# 02_V5_IO1.net
KiCad netlist of a schematic drawn in Altium Designer
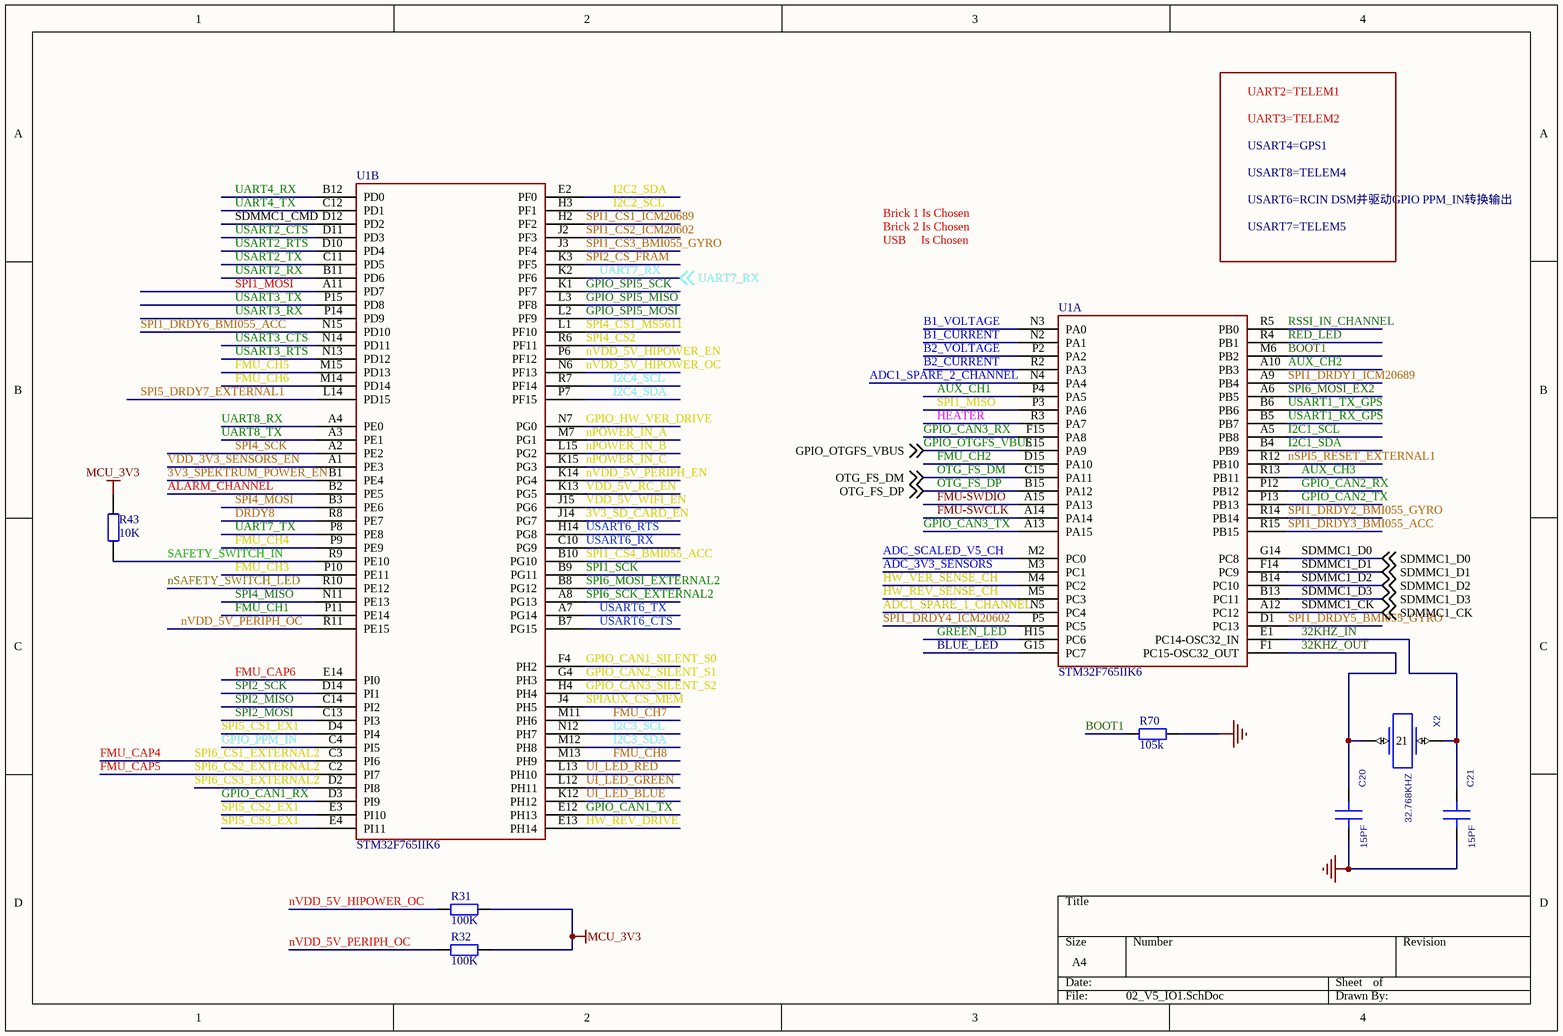
[diagram p0: 02_V5_IO1.SchDoc]

(export (version "E")
  (design (tool "Eeschema 10.0.6"))
  (components
    (comp (ref "C20") (value "15PF") (footprint "SC0402") (libsource (lib "*") (part "C")))
    (comp (ref "C21") (value "15PF") (footprint "SC0402") (libsource (lib "*") (part "C")))
    (comp (ref "R31")
      (value "100K")
      (description "Resistor")
      (fields (field (name "PUBLISHER") "Altium Limited"))
      (libsource (lib "Miscellaneous Devices") (part "Res2"))
    )
    (comp (ref "R32")
      (value "100K")
      (description "Resistor")
      (fields (field (name "PUBLISHER") "Altium Limited"))
      (libsource (lib "Miscellaneous Devices") (part "Res2"))
    )
    (comp (ref "R43")
      (value "10K")
      (footprint "0402R")
      (description "0402R0R 1%")
      (libsource (lib "CUAV") (part "0402R0R"))
    )
    (comp (ref "R70")
      (value "105k")
      (description "Resistor")
      (fields (field (name "PUBLISHER") "Altium Limited"))
      (libsource (lib "Miscellaneous Devices") (part "Res2"))
    )
    (comp (ref "U1")
      (value "STM32F765IIK6")
      (footprint "UFBGA176")
      (libsource (lib "CUAV") (part "STM32F765IIK6"))
    )
    (comp (ref "X2") (value "32.768KHZ") (footprint "ABS06") (libsource (lib "*") (part "X_0")))
  )
  (nets
    (net (code "1") (name "/3V3_SD_CARD_EN") (class "Default")
      (node (ref "U1") (pin "J14") (pinfunction "PG7_J14") (pintype "passive"))
    )
    (net (code "2") (name "/3V3_SPEKTRUM_POWER_EN") (class "Default")
      (node (ref "U1") (pin "B1") (pinfunction "PE4_B1") (pintype "passive"))
    )
    (net (code "3") (name "/32KHZ_IN") (class "Default")
      (node (ref "C21") (pin "1") (pinfunction "A_1") (pintype "bidirectional"))
      (node (ref "U1") (pin "E1") (pinfunction "PC14-OSC32_IN_E1") (pintype "passive"))
      (node (ref "X2") (pin "1") (pinfunction "1_1") (pintype "bidirectional"))
    )
    (net (code "4") (name "/32KHZ_OUT") (class "Default")
      (node (ref "C20") (pin "1") (pinfunction "A_1") (pintype "bidirectional"))
      (node (ref "U1") (pin "F1") (pinfunction "PC15-OSC32_OUT_F1") (pintype "passive"))
      (node (ref "X2") (pin "2") (pinfunction "2_2") (pintype "bidirectional"))
    )
    (net (code "5") (name "/ADC1_SPARE_1_CHANNEL") (class "Default")
      (node (ref "U1") (pin "N5") (pinfunction "PC4_N5") (pintype "passive"))
    )
    (net (code "6") (name "/ADC1_SPARE_2_CHANNEL") (class "Default")
      (node (ref "U1") (pin "N4") (pinfunction "PA4_N4") (pintype "passive"))
    )
    (net (code "7") (name "/ADC_3V3_SENSORS") (class "Default")
      (node (ref "U1") (pin "M3") (pinfunction "PC1_M3") (pintype "passive"))
    )
    (net (code "8") (name "/ADC_SCALED_V5_CH") (class "Default")
      (node (ref "U1") (pin "M2") (pinfunction "PC0_M2") (pintype "passive"))
    )
    (net (code "9") (name "/ALARM_CHANNEL") (class "Default")
      (node (ref "U1") (pin "B2") (pinfunction "PE5_B2") (pintype "passive"))
    )
    (net (code "10") (name "/AUX_CH1") (class "Default")
      (node (ref "U1") (pin "P4") (pinfunction "PA5_P4") (pintype "passive"))
    )
    (net (code "11") (name "/AUX_CH2") (class "Default")
      (node (ref "U1") (pin "A10") (pinfunction "PB3_A10") (pintype "passive"))
    )
    (net (code "12") (name "/AUX_CH3") (class "Default")
      (node (ref "U1") (pin "R13") (pinfunction "PB11_R13") (pintype "passive"))
    )
    (net (code "13") (name "/B1_CURRENT") (class "Default")
      (node (ref "U1") (pin "N2") (pinfunction "PA1_N2") (pintype "passive"))
    )
    (net (code "14") (name "/B1_VOLTAGE") (class "Default")
      (node (ref "U1") (pin "N3") (pinfunction "PA0_N3") (pintype "passive"))
    )
    (net (code "15") (name "/B2_CURRENT") (class "Default")
      (node (ref "U1") (pin "R2") (pinfunction "PA3_R2") (pintype "passive"))
    )
    (net (code "16") (name "/B2_VOLTAGE") (class "Default")
      (node (ref "U1") (pin "P2") (pinfunction "PA2_P2") (pintype "passive"))
    )
    (net (code "17") (name "/BLUE_LED") (class "Default")
      (node (ref "U1") (pin "G15") (pinfunction "PC7_G15") (pintype "passive"))
    )
    (net (code "18") (name "/BOOT1") (class "Default")
      (node (ref "R70") (pin "1") (pinfunction "1_1") (pintype "passive"))
      (node (ref "U1") (pin "M6") (pinfunction "PB2_M6") (pintype "passive"))
    )
    (net (code "21") (name "/DRDY8") (class "Default")
      (node (ref "U1") (pin "R8") (pinfunction "PE7_R8") (pintype "passive"))
    )
    (net (code "22") (name "/FMU-SWCLK") (class "Default")
      (node (ref "U1") (pin "A14") (pinfunction "PA14_A14") (pintype "passive"))
    )
    (net (code "23") (name "/FMU-SWDIO") (class "Default")
      (node (ref "U1") (pin "A15") (pinfunction "PA13_A15") (pintype "passive"))
    )
    (net (code "24") (name "/FMU_CAP4") (class "Default")
      (node (ref "U1") (pin "C3") (pinfunction "PI6_C3") (pintype "passive"))
    )
    (net (code "25") (name "/FMU_CAP5") (class "Default")
      (node (ref "U1") (pin "C2") (pinfunction "PI7_C2") (pintype "passive"))
    )
    (net (code "26") (name "/FMU_CAP6") (class "Default")
      (node (ref "U1") (pin "E14") (pinfunction "PI0_E14") (pintype "passive"))
    )
    (net (code "27") (name "/FMU_CH1") (class "Default")
      (node (ref "U1") (pin "P11") (pinfunction "PE14_P11") (pintype "passive"))
    )
    (net (code "28") (name "/FMU_CH2") (class "Default")
      (node (ref "U1") (pin "D15") (pinfunction "PA10_D15") (pintype "passive"))
    )
    (net (code "29") (name "/FMU_CH3") (class "Default")
      (node (ref "U1") (pin "P10") (pinfunction "PE11_P10") (pintype "passive"))
    )
    (net (code "30") (name "/FMU_CH4") (class "Default")
      (node (ref "U1") (pin "P9") (pinfunction "PE9_P9") (pintype "passive"))
    )
    (net (code "31") (name "/FMU_CH5") (class "Default")
      (node (ref "U1") (pin "M15") (pinfunction "PD13_M15") (pintype "passive"))
    )
    (net (code "32") (name "/FMU_CH6") (class "Default")
      (node (ref "U1") (pin "M14") (pinfunction "PD14_M14") (pintype "passive"))
    )
    (net (code "33") (name "/FMU_CH7") (class "Default")
      (node (ref "U1") (pin "M11") (pinfunction "PH6_M11") (pintype "passive"))
    )
    (net (code "34") (name "/FMU_CH8") (class "Default")
      (node (ref "U1") (pin "M13") (pinfunction "PH9_M13") (pintype "passive"))
    )
    (net (code "35") (name "/GPIO_CAN1_RX") (class "Default")
      (node (ref "U1") (pin "D3") (pinfunction "PI9_D3") (pintype "passive"))
    )
    (net (code "36") (name "/GPIO_CAN1_SILENT_S0") (class "Default")
      (node (ref "U1") (pin "F4") (pinfunction "PH2_F4") (pintype "passive"))
    )
    (net (code "37") (name "/GPIO_CAN1_TX") (class "Default")
      (node (ref "U1") (pin "E12") (pinfunction "PH13_E12") (pintype "passive"))
    )
    (net (code "38") (name "/GPIO_CAN2_RX") (class "Default")
      (node (ref "U1") (pin "P12") (pinfunction "PB12_P12") (pintype "passive"))
    )
    (net (code "39") (name "/GPIO_CAN2_SILENT_S1") (class "Default")
      (node (ref "U1") (pin "G4") (pinfunction "PH3_G4") (pintype "passive"))
    )
    (net (code "40") (name "/GPIO_CAN2_TX") (class "Default")
      (node (ref "U1") (pin "P13") (pinfunction "PB13_P13") (pintype "passive"))
    )
    (net (code "41") (name "/GPIO_CAN3_RX") (class "Default")
      (node (ref "U1") (pin "F15") (pinfunction "PA8_F15") (pintype "passive"))
    )
    (net (code "42") (name "/GPIO_CAN3_SILENT_S2") (class "Default")
      (node (ref "U1") (pin "H4") (pinfunction "PH4_H4") (pintype "passive"))
    )
    (net (code "43") (name "/GPIO_CAN3_TX") (class "Default")
      (node (ref "U1") (pin "A13") (pinfunction "PA15_A13") (pintype "passive"))
    )
    (net (code "44") (name "/GPIO_HW_VER_DRIVE") (class "Default")
      (node (ref "U1") (pin "N7") (pinfunction "PG0_N7") (pintype "passive"))
    )
    (net (code "45") (name "/GPIO_PPM_IN") (class "Default")
      (node (ref "U1") (pin "C4") (pinfunction "PI5_C4") (pintype "passive"))
    )
    (net (code "46") (name "/GPIO_SPI5_MISO") (class "Default")
      (node (ref "U1") (pin "L3") (pinfunction "PF8_L3") (pintype "passive"))
    )
    (net (code "47") (name "/GPIO_SPI5_MOSI") (class "Default")
      (node (ref "U1") (pin "L2") (pinfunction "PF9_L2") (pintype "passive"))
    )
    (net (code "48") (name "/GPIO_SPI5_SCK") (class "Default")
      (node (ref "U1") (pin "K1") (pinfunction "PF7_K1") (pintype "passive"))
    )
    (net (code "49") (name "/GREEN_LED") (class "Default")
      (node (ref "U1") (pin "H15") (pinfunction "PC6_H15") (pintype "passive"))
    )
    (net (code "50") (name "/HEATER") (class "Default")
      (node (ref "U1") (pin "R3") (pinfunction "PA7_R3") (pintype "passive"))
    )
    (net (code "51") (name "/HW_REV_DRIVE") (class "Default")
      (node (ref "U1") (pin "E13") (pinfunction "PH14_E13") (pintype "passive"))
    )
    (net (code "52") (name "/HW_REV_SENSE_CH") (class "Default")
      (node (ref "U1") (pin "M5") (pinfunction "PC3_M5") (pintype "passive"))
    )
    (net (code "53") (name "/HW_VER_SENSE_CH") (class "Default")
      (node (ref "U1") (pin "M4") (pinfunction "PC2_M4") (pintype "passive"))
    )
    (net (code "54") (name "/I2C1_SCL") (class "Default")
      (node (ref "U1") (pin "A5") (pinfunction "PB8_A5") (pintype "passive"))
    )
    (net (code "55") (name "/I2C1_SDA") (class "Default")
      (node (ref "U1") (pin "B4") (pinfunction "PB9_B4") (pintype "passive"))
    )
    (net (code "56") (name "/I2C2_SCL") (class "Default")
      (node (ref "U1") (pin "H3") (pinfunction "PF1_H3") (pintype "passive"))
    )
    (net (code "57") (name "/I2C2_SDA") (class "Default")
      (node (ref "U1") (pin "E2") (pinfunction "PF0_E2") (pintype "passive"))
    )
    (net (code "58") (name "/I2C3_SCL") (class "Default")
      (node (ref "U1") (pin "N12") (pinfunction "PH7_N12") (pintype "passive"))
    )
    (net (code "59") (name "/I2C3_SDA") (class "Default")
      (node (ref "U1") (pin "M12") (pinfunction "PH8_M12") (pintype "passive"))
    )
    (net (code "60") (name "/I2C4_SCL") (class "Default")
      (node (ref "U1") (pin "R7") (pinfunction "PF14_R7") (pintype "passive"))
    )
    (net (code "61") (name "/I2C4_SDA") (class "Default")
      (node (ref "U1") (pin "P7") (pinfunction "PF15_P7") (pintype "passive"))
    )
    (net (code "62") (name "/RED_LED") (class "Default")
      (node (ref "U1") (pin "R4") (pinfunction "PB1_R4") (pintype "passive"))
    )
    (net (code "63") (name "/RSSI_IN_CHANNEL") (class "Default")
      (node (ref "U1") (pin "R5") (pinfunction "PB0_R5") (pintype "passive"))
    )
    (net (code "64") (name "/SAFETY_SWITCH_IN") (class "Default")
      (node (ref "R43") (pin "2") (pintype "passive"))
      (node (ref "U1") (pin "R9") (pinfunction "PE10_R9") (pintype "passive"))
    )
    (net (code "65") (name "/SDMMC1_CMD") (class "Default")
      (node (ref "U1") (pin "D12") (pinfunction "PD2_D12") (pintype "passive"))
    )
    (net (code "66") (name "/SPI1_CS1_ICM20689") (class "Default")
      (node (ref "U1") (pin "H2") (pinfunction "PF2_H2") (pintype "passive"))
    )
    (net (code "67") (name "/SPI1_CS2_ICM20602") (class "Default")
      (node (ref "U1") (pin "J2") (pinfunction "PF3_J2") (pintype "passive"))
    )
    (net (code "68") (name "/SPI1_CS3_BMI055_GYRO") (class "Default")
      (node (ref "U1") (pin "J3") (pinfunction "PF4_J3") (pintype "passive"))
    )
    (net (code "69") (name "/SPI1_CS4_BMI055_ACC") (class "Default")
      (node (ref "U1") (pin "B10") (pinfunction "PG10_B10") (pintype "passive"))
    )
    (net (code "70") (name "/SPI1_DRDY1_ICM20689") (class "Default")
      (node (ref "U1") (pin "A9") (pinfunction "PB4_A9") (pintype "passive"))
    )
    (net (code "71") (name "/SPI1_DRDY2_BMI055_GYRO") (class "Default")
      (node (ref "U1") (pin "R14") (pinfunction "PB14_R14") (pintype "passive"))
    )
    (net (code "72") (name "/SPI1_DRDY3_BMI055_ACC") (class "Default")
      (node (ref "U1") (pin "R15") (pinfunction "PB15_R15") (pintype "passive"))
    )
    (net (code "73") (name "/SPI1_DRDY4_ICM20602") (class "Default")
      (node (ref "U1") (pin "P5") (pinfunction "PC5_P5") (pintype "passive"))
    )
    (net (code "74") (name "/SPI1_DRDY5_BMI055_GYRO") (class "Default")
      (node (ref "U1") (pin "D1") (pinfunction "PC13_D1") (pintype "passive"))
    )
    (net (code "75") (name "/SPI1_DRDY6_BMI055_ACC") (class "Default")
      (node (ref "U1") (pin "N15") (pinfunction "PD10_N15") (pintype "passive"))
    )
    (net (code "76") (name "/SPI1_MISO") (class "Default")
      (node (ref "U1") (pin "P3") (pinfunction "PA6_P3") (pintype "passive"))
    )
    (net (code "77") (name "/SPI1_MOSI") (class "Default")
      (node (ref "U1") (pin "A11") (pinfunction "PD7_A11") (pintype "passive"))
    )
    (net (code "78") (name "/SPI1_SCK") (class "Default")
      (node (ref "U1") (pin "B9") (pinfunction "PG11_B9") (pintype "passive"))
    )
    (net (code "79") (name "/SPI2_CS_FRAM") (class "Default")
      (node (ref "U1") (pin "K3") (pinfunction "PF5_K3") (pintype "passive"))
    )
    (net (code "80") (name "/SPI2_MISO") (class "Default")
      (node (ref "U1") (pin "C14") (pinfunction "PI2_C14") (pintype "passive"))
    )
    (net (code "81") (name "/SPI2_MOSI") (class "Default")
      (node (ref "U1") (pin "C13") (pinfunction "PI3_C13") (pintype "passive"))
    )
    (net (code "82") (name "/SPI2_SCK") (class "Default")
      (node (ref "U1") (pin "D14") (pinfunction "PI1_D14") (pintype "passive"))
    )
    (net (code "83") (name "/SPI4_CS1_MS5611") (class "Default")
      (node (ref "U1") (pin "L1") (pinfunction "PF10_L1") (pintype "passive"))
    )
    (net (code "84") (name "/SPI4_CS2") (class "Default")
      (node (ref "U1") (pin "R6") (pinfunction "PF11_R6") (pintype "passive"))
    )
    (net (code "85") (name "/SPI4_MISO") (class "Default")
      (node (ref "U1") (pin "N11") (pinfunction "PE13_N11") (pintype "passive"))
    )
    (net (code "86") (name "/SPI4_MOSI") (class "Default")
      (node (ref "U1") (pin "B3") (pinfunction "PE6_B3") (pintype "passive"))
    )
    (net (code "87") (name "/SPI4_SCK") (class "Default")
      (node (ref "U1") (pin "A2") (pinfunction "PE2_A2") (pintype "passive"))
    )
    (net (code "88") (name "/SPI5_CS1_EX1") (class "Default")
      (node (ref "U1") (pin "D4") (pinfunction "PI4_D4") (pintype "passive"))
    )
    (net (code "89") (name "/SPI5_CS2_EX1") (class "Default")
      (node (ref "U1") (pin "E3") (pinfunction "PI10_E3") (pintype "passive"))
    )
    (net (code "90") (name "/SPI5_CS3_EX1") (class "Default")
      (node (ref "U1") (pin "E4") (pinfunction "PI11_E4") (pintype "passive"))
    )
    (net (code "91") (name "/SPI5_DRDY7_EXTERNAL1") (class "Default")
      (node (ref "U1") (pin "L14") (pinfunction "PD15_L14") (pintype "passive"))
    )
    (net (code "92") (name "/SPI6_CS3_EXTERNAL2") (class "Default")
      (node (ref "U1") (pin "D2") (pinfunction "PI8_D2") (pintype "passive"))
    )
    (net (code "93") (name "/SPI6_MOSI_EX2") (class "Default")
      (node (ref "U1") (pin "A6") (pinfunction "PB5_A6") (pintype "passive"))
    )
    (net (code "94") (name "/SPI6_MOSI_EXTERNAL2") (class "Default")
      (node (ref "U1") (pin "B8") (pinfunction "PG12_B8") (pintype "passive"))
    )
    (net (code "95") (name "/SPI6_SCK_EXTERNAL2") (class "Default")
      (node (ref "U1") (pin "A8") (pinfunction "PG13_A8") (pintype "passive"))
    )
    (net (code "96") (name "/SPIAUX_CS_MEM") (class "Default")
      (node (ref "U1") (pin "J4") (pinfunction "PH5_J4") (pintype "passive"))
    )
    (net (code "99") (name "/UART4_RX") (class "Default")
      (node (ref "U1") (pin "B12") (pinfunction "PD0_B12") (pintype "passive"))
    )
    (net (code "100") (name "/UART4_TX") (class "Default")
      (node (ref "U1") (pin "C12") (pinfunction "PD1_C12") (pintype "passive"))
    )
    (net (code "101") (name "/UART7_TX") (class "Default")
      (node (ref "U1") (pin "P8") (pinfunction "PE8_P8") (pintype "passive"))
    )
    (net (code "102") (name "/UART8_RX") (class "Default")
      (node (ref "U1") (pin "A4") (pinfunction "PE0_A4") (pintype "passive"))
    )
    (net (code "103") (name "/UART8_TX") (class "Default")
      (node (ref "U1") (pin "A3") (pinfunction "PE1_A3") (pintype "passive"))
    )
    (net (code "104") (name "/UI_LED_BLUE") (class "Default")
      (node (ref "U1") (pin "K12") (pinfunction "PH12_K12") (pintype "passive"))
    )
    (net (code "105") (name "/UI_LED_GREEN") (class "Default")
      (node (ref "U1") (pin "L12") (pinfunction "PH11_L12") (pintype "passive"))
    )
    (net (code "106") (name "/UI_LED_RED") (class "Default")
      (node (ref "U1") (pin "L13") (pinfunction "PH10_L13") (pintype "passive"))
    )
    (net (code "107") (name "/USART1_RX_GPS") (class "Default")
      (node (ref "U1") (pin "B5") (pinfunction "PB7_B5") (pintype "passive"))
    )
    (net (code "108") (name "/USART1_TX_GPS") (class "Default")
      (node (ref "U1") (pin "B6") (pinfunction "PB6_B6") (pintype "passive"))
    )
    (net (code "109") (name "/USART2_CTS") (class "Default")
      (node (ref "U1") (pin "D11") (pinfunction "PD3_D11") (pintype "passive"))
    )
    (net (code "110") (name "/USART2_RTS") (class "Default")
      (node (ref "U1") (pin "D10") (pinfunction "PD4_D10") (pintype "passive"))
    )
    (net (code "111") (name "/USART2_RX") (class "Default")
      (node (ref "U1") (pin "B11") (pinfunction "PD6_B11") (pintype "passive"))
    )
    (net (code "112") (name "/USART2_TX") (class "Default")
      (node (ref "U1") (pin "C11") (pinfunction "PD5_C11") (pintype "passive"))
    )
    (net (code "113") (name "/USART3_CTS") (class "Default")
      (node (ref "U1") (pin "N14") (pinfunction "PD11_N14") (pintype "passive"))
    )
    (net (code "114") (name "/USART3_RTS") (class "Default")
      (node (ref "U1") (pin "N13") (pinfunction "PD12_N13") (pintype "passive"))
    )
    (net (code "115") (name "/USART3_RX") (class "Default")
      (node (ref "U1") (pin "P14") (pinfunction "PD9_P14") (pintype "passive"))
    )
    (net (code "116") (name "/USART3_TX") (class "Default")
      (node (ref "U1") (pin "P15") (pinfunction "PD8_P15") (pintype "passive"))
    )
    (net (code "119") (name "/USART6_CTS") (class "Default")
      (node (ref "U1") (pin "B7") (pinfunction "PG15_B7") (pintype "passive"))
    )
    (net (code "120") (name "/USART6_RTS") (class "Default")
      (node (ref "U1") (pin "H14") (pinfunction "PG8_H14") (pintype "passive"))
    )
    (net (code "121") (name "/USART6_RX") (class "Default")
      (node (ref "U1") (pin "C10") (pinfunction "PG9_C10") (pintype "passive"))
    )
    (net (code "122") (name "/USART6_TX") (class "Default")
      (node (ref "U1") (pin "A7") (pinfunction "PG14_A7") (pintype "passive"))
    )
    (net (code "126") (name "/VDD_3V3_SENSORS_EN") (class "Default")
      (node (ref "U1") (pin "A1") (pinfunction "PE3_A1") (pintype "passive"))
    )
    (net (code "127") (name "/VDD_5V_RC_EN") (class "Default")
      (node (ref "U1") (pin "K13") (pinfunction "PG5_K13") (pintype "passive"))
    )
    (net (code "128") (name "/VDD_5V_WIFI_EN") (class "Default")
      (node (ref "U1") (pin "J15") (pinfunction "PG6_J15") (pintype "passive"))
    )
    (net (code "129") (name "/nPOWER_IN_A") (class "Default")
      (node (ref "U1") (pin "M7") (pinfunction "PG1_M7") (pintype "passive"))
    )
    (net (code "130") (name "/nPOWER_IN_B") (class "Default")
      (node (ref "U1") (pin "L15") (pinfunction "PG2_L15") (pintype "passive"))
    )
    (net (code "131") (name "/nPOWER_IN_C") (class "Default")
      (node (ref "U1") (pin "K15") (pinfunction "PG3_K15") (pintype "passive"))
    )
    (net (code "132") (name "/nSAFETY_SWITCH_LED") (class "Default")
      (node (ref "U1") (pin "R10") (pinfunction "PE12_R10") (pintype "passive"))
    )
    (net (code "133") (name "/nSPI5_RESET_EXTERNAL1") (class "Default")
      (node (ref "U1") (pin "R12") (pinfunction "PB10_R12") (pintype "passive"))
    )
    (net (code "134") (name "/nVDD_5V_HIPOWER_EN") (class "Default")
      (node (ref "U1") (pin "P6") (pinfunction "PF12_P6") (pintype "passive"))
    )
    (net (code "135") (name "/nVDD_5V_HIPOWER_OC") (class "Default")
      (node (ref "R31") (pin "1") (pinfunction "1_1") (pintype "passive"))
      (node (ref "U1") (pin "N6") (pinfunction "PF13_N6") (pintype "passive"))
    )
    (net (code "136") (name "/nVDD_5V_PERIPH_EN") (class "Default")
      (node (ref "U1") (pin "K14") (pinfunction "PG4_K14") (pintype "passive"))
    )
    (net (code "137") (name "/nVDD_5V_PERIPH_OC") (class "Default")
      (node (ref "R32") (pin "1") (pinfunction "1_1") (pintype "passive"))
      (node (ref "U1") (pin "R11") (pinfunction "PE15_R11") (pintype "passive"))
    )
    (net (code "138") (name "GND") (class "Default")
      (node (ref "C20") (pin "2") (pinfunction "B_2") (pintype "bidirectional"))
      (node (ref "C21") (pin "2") (pinfunction "B_2") (pintype "bidirectional"))
      (node (ref "R70") (pin "2") (pinfunction "2_2") (pintype "passive"))
    )
    (net (code "139") (name "GPIO_OTGFS_VBUS") (class "Default")
      (node (ref "U1") (pin "E15") (pinfunction "PA9_E15") (pintype "passive"))
    )
    (net (code "140") (name "MCU_3V3") (class "Default")
      (node (ref "R31") (pin "2") (pinfunction "2_2") (pintype "passive"))
      (node (ref "R32") (pin "2") (pinfunction "2_2") (pintype "passive"))
      (node (ref "R43") (pin "1") (pintype "passive"))
    )
    (net (code "141") (name "OTG_FS_DM") (class "Default")
      (node (ref "U1") (pin "C15") (pinfunction "PA11_C15") (pintype "passive"))
    )
    (net (code "142") (name "OTG_FS_DP") (class "Default")
      (node (ref "U1") (pin "B15") (pinfunction "PA12_B15") (pintype "passive"))
    )
    (net (code "143") (name "SDMMC1_CK") (class "Default")
      (node (ref "U1") (pin "A12") (pinfunction "PC12_A12") (pintype "passive"))
    )
    (net (code "144") (name "SDMMC1_D0") (class "Default")
      (node (ref "U1") (pin "G14") (pinfunction "PC8_G14") (pintype "passive"))
    )
    (net (code "145") (name "SDMMC1_D1") (class "Default")
      (node (ref "U1") (pin "F14") (pinfunction "PC9_F14") (pintype "passive"))
    )
    (net (code "146") (name "SDMMC1_D2") (class "Default")
      (node (ref "U1") (pin "B14") (pinfunction "PC10_B14") (pintype "passive"))
    )
    (net (code "147") (name "SDMMC1_D3") (class "Default")
      (node (ref "U1") (pin "B13") (pinfunction "PC11_B13") (pintype "passive"))
    )
    (net (code "148") (name "UART7_RX") (class "Default")
      (node (ref "U1") (pin "K2") (pinfunction "PF6_K2") (pintype "passive"))
    )
  )
)
